# Car.net
KiCad netlist of a schematic drawn in Altium Designer
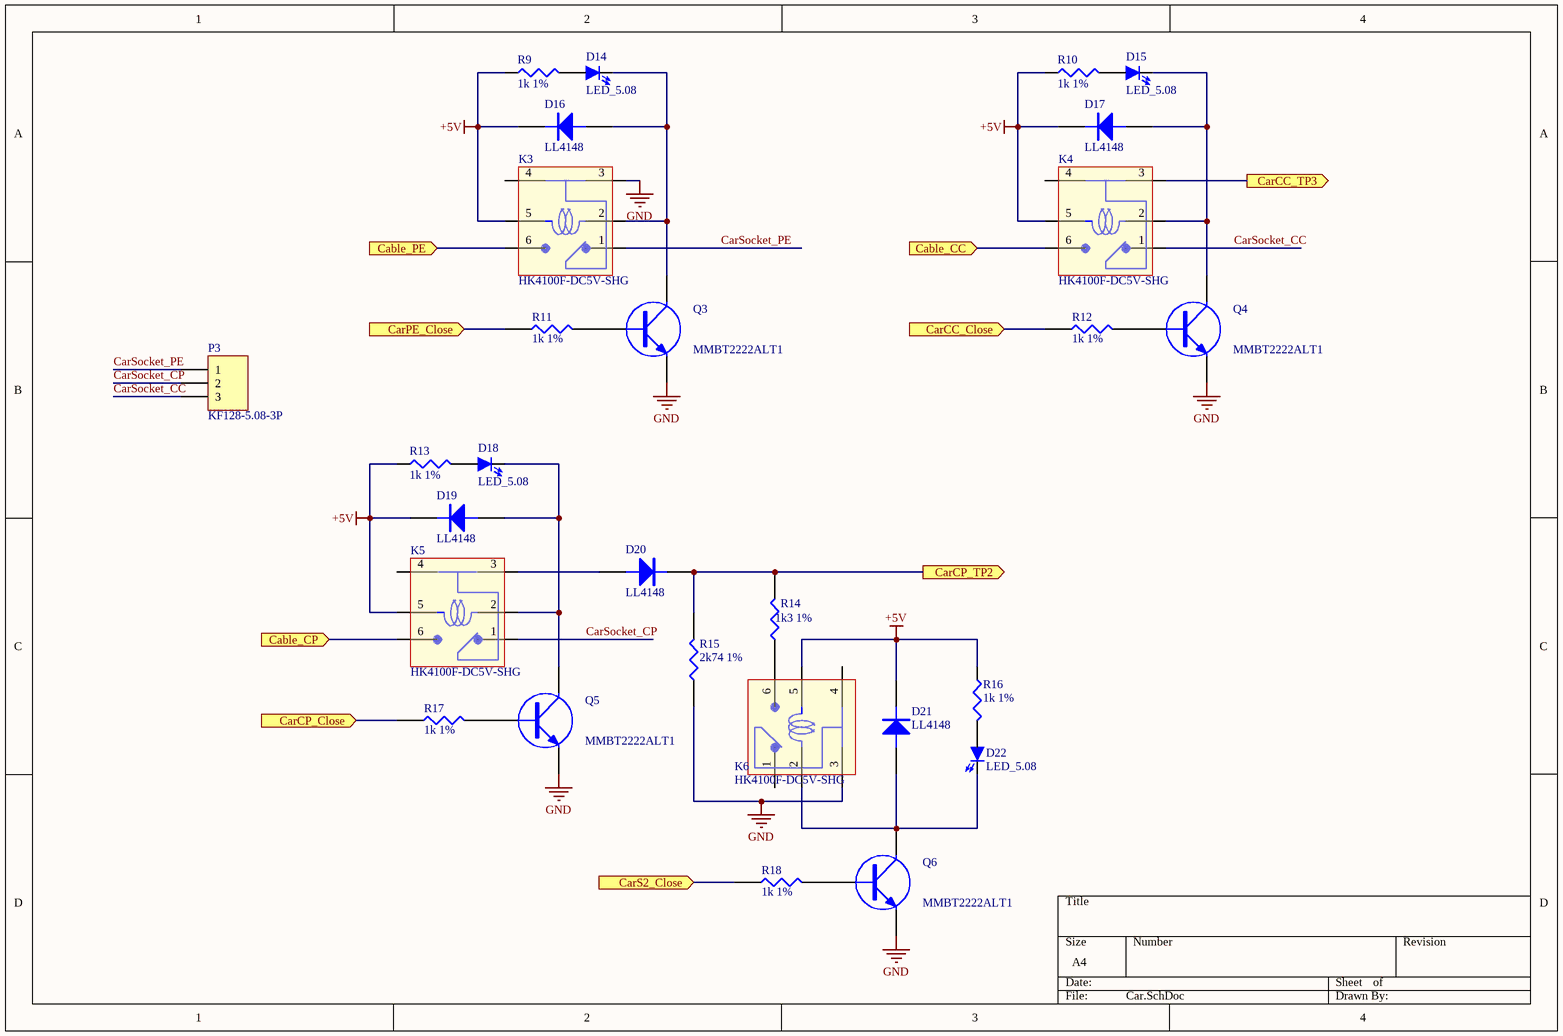
[diagram p0: Car.SchDoc]

(export (version "E")
  (design (tool "Eeschema 10.0.6"))
  (components
    (comp (ref "D14")
      (value "LED_5.08")
      (footprint "UserPcbLib:LED5.08/2.54-2")
      (description "Through hole LED dia.5.08")
      (libsource (lib "UserSchlib") (part "LED_5.08"))
    )
    (comp (ref "D15")
      (value "LED_5.08")
      (footprint "UserPcbLib:LED5.08/2.54-2")
      (description "Through hole LED dia.5.08")
      (libsource (lib "UserSchlib") (part "LED_5.08"))
    )
    (comp (ref "D16")
      (value "LL4148")
      (footprint "MELF - Diode:MELF-D3513-1405")
      (description "Diode")
      (libsource (lib "*") (part "DIODE"))
    )
    (comp (ref "D17")
      (value "LL4148")
      (footprint "MELF - Diode:MELF-D3513-1405")
      (description "Diode")
      (libsource (lib "*") (part "DIODE"))
    )
    (comp (ref "D18")
      (value "LED_5.08")
      (footprint "UserPcbLib:LED5.08/2.54-2")
      (description "Through hole LED dia.5.08")
      (libsource (lib "UserSchlib") (part "LED_5.08"))
    )
    (comp (ref "D19")
      (value "LL4148")
      (footprint "MELF - Diode:MELF-D3513-1405")
      (description "Diode")
      (libsource (lib "*") (part "DIODE"))
    )
    (comp (ref "D20")
      (value "LL4148")
      (footprint "MELF - Diode:MELF-D3513-1405")
      (description "Diode")
      (libsource (lib "*") (part "DIODE"))
    )
    (comp (ref "D21")
      (value "LL4148")
      (footprint "MELF - Diode:MELF-D3513-1405")
      (description "Diode")
      (libsource (lib "*") (part "DIODE"))
    )
    (comp (ref "D22")
      (value "LED_5.08")
      (footprint "UserPcbLib:LED5.08/2.54-2")
      (description "Through hole LED dia.5.08")
      (libsource (lib "UserSchlib") (part "LED_5.08"))
    )
    (comp (ref "K3")
      (value "HK4100F-DC5V-SHG")
      (footprint "UserPcbLib:HK4100F-DC5V-SHG")
      (description "HUI KE DC5V relay")
      (libsource (lib "UserSchlib") (part "HK4100F-DC5V-SHG"))
    )
    (comp (ref "K4")
      (value "HK4100F-DC5V-SHG")
      (footprint "UserPcbLib:HK4100F-DC5V-SHG")
      (description "HUI KE DC5V relay")
      (libsource (lib "UserSchlib") (part "HK4100F-DC5V-SHG"))
    )
    (comp (ref "K5")
      (value "HK4100F-DC5V-SHG")
      (footprint "UserPcbLib:HK4100F-DC5V-SHG")
      (description "HUI KE DC5V relay")
      (libsource (lib "UserSchlib") (part "HK4100F-DC5V-SHG"))
    )
    (comp (ref "K6")
      (value "HK4100F-DC5V-SHG")
      (footprint "UserPcbLib:HK4100F-DC5V-SHG")
      (description "HUI KE DC5V relay")
      (libsource (lib "") (part "HK4100F-DC5V-SHG_1"))
    )
    (comp (ref "P3")
      (value "KF128-5.08-3P")
      (footprint "UserPcbLib:KF128-5.08-3P")
      (description "Car socket connector")
      (fields (field (name "PUBLISHER") "Altium Limited"))
      (libsource (lib "Miscellaneous Connectors") (part "Header 3"))
    )
    (comp (ref "Q3") (value "MMBT2222ALT1") (footprint "SOT23_M:SOT23-3M") (libsource (lib "*") (part "NPN")))
    (comp (ref "Q4") (value "MMBT2222ALT1") (footprint "SOT23_M:SOT23-3M") (libsource (lib "*") (part "NPN")))
    (comp (ref "Q5") (value "MMBT2222ALT1") (footprint "SOT23_M:SOT23-3M") (libsource (lib "*") (part "NPN")))
    (comp (ref "Q6") (value "MMBT2222ALT1") (footprint "SOT23_M:SOT23-3M") (libsource (lib "*") (part "NPN")))
    (comp (ref "R9")
      (value "1k 1%")
      (footprint "Chip_Resistor_N:RESC2012N")
      (description "Resistor")
      (libsource (lib "Miscellaneous Devices") (part "Res3"))
    )
    (comp (ref "R10")
      (value "1k 1%")
      (footprint "Chip_Resistor_N:RESC2012N")
      (description "Resistor")
      (libsource (lib "Miscellaneous Devices") (part "Res3"))
    )
    (comp (ref "R11")
      (value "1k 1%")
      (footprint "Chip_Resistor_N:RESC2012N")
      (libsource (lib "*") (part "RES1"))
    )
    (comp (ref "R12")
      (value "1k 1%")
      (footprint "Chip_Resistor_N:RESC2012N")
      (libsource (lib "*") (part "RES1"))
    )
    (comp (ref "R13")
      (value "1k 1%")
      (footprint "Chip_Resistor_N:RESC2012N")
      (description "Resistor")
      (libsource (lib "Miscellaneous Devices") (part "Res3"))
    )
    (comp (ref "R14")
      (value "1k3 1%")
      (footprint "Chip_Resistor_N:RESC2012N")
      (libsource (lib "*") (part "RES1"))
    )
    (comp (ref "R15")
      (value "2k74 1%")
      (footprint "Chip_Resistor_N:RESC2012N")
      (libsource (lib "*") (part "RES1"))
    )
    (comp (ref "R16")
      (value "1k 1%")
      (footprint "Chip_Resistor_N:RESC2012N")
      (description "Resistor")
      (libsource (lib "Miscellaneous Devices") (part "Res3"))
    )
    (comp (ref "R17")
      (value "1k 1%")
      (footprint "Chip_Resistor_N:RESC2012N")
      (libsource (lib "*") (part "RES1"))
    )
    (comp (ref "R18")
      (value "1k 1%")
      (footprint "Chip_Resistor_N:RESC2012N")
      (libsource (lib "*") (part "RES1"))
    )
  )
  (nets
    (net (code "1") (name "+5V") (class "Default")
      (node (ref "D16") (pin "2") (pinfunction "K_2") (pintype "passive"))
      (node (ref "D17") (pin "2") (pinfunction "K_2") (pintype "passive"))
      (node (ref "D19") (pin "2") (pinfunction "K_2") (pintype "passive"))
      (node (ref "D21") (pin "2") (pinfunction "K_2") (pintype "passive"))
      (node (ref "K3") (pin "5") (pinfunction "5_5") (pintype "passive"))
      (node (ref "K4") (pin "5") (pinfunction "5_5") (pintype "passive"))
      (node (ref "K5") (pin "5") (pinfunction "5_5") (pintype "passive"))
      (node (ref "K6") (pin "5") (pinfunction "5_5") (pintype "passive"))
      (node (ref "R10") (pin "1") (pinfunction "1_1") (pintype "passive"))
      (node (ref "R13") (pin "1") (pinfunction "1_1") (pintype "passive"))
      (node (ref "R16") (pin "1") (pinfunction "1_1") (pintype "passive"))
      (node (ref "R9") (pin "1") (pinfunction "1_1") (pintype "passive"))
    )
    (net (code "2") (name "/Cable_CC") (class "Default")
      (node (ref "K4") (pin "6") (pinfunction "6_6") (pintype "passive"))
    )
    (net (code "3") (name "/Cable_CP") (class "Default")
      (node (ref "K5") (pin "6") (pinfunction "6_6") (pintype "passive"))
    )
    (net (code "4") (name "/Cable_PE") (class "Default")
      (node (ref "K3") (pin "6") (pinfunction "6_6") (pintype "passive"))
    )
    (net (code "5") (name "/CarCC_Close") (class "Default")
      (node (ref "R12") (pin "1") (pinfunction "1_1") (pintype "passive"))
    )
    (net (code "6") (name "/CarCC_TP3") (class "Default")
      (node (ref "K4") (pin "3") (pinfunction "3_3") (pintype "passive"))
    )
    (net (code "7") (name "/CarCP_Close") (class "Default")
      (node (ref "R17") (pin "1") (pinfunction "1_1") (pintype "passive"))
    )
    (net (code "8") (name "/CarCP_TP2") (class "Default")
      (node (ref "D20") (pin "2") (pinfunction "K_2") (pintype "passive"))
      (node (ref "R14") (pin "2") (pinfunction "2_2") (pintype "passive"))
      (node (ref "R15") (pin "2") (pinfunction "2_2") (pintype "passive"))
    )
    (net (code "9") (name "/CarPE_Close") (class "Default")
      (node (ref "R11") (pin "1") (pinfunction "1_1") (pintype "passive"))
    )
    (net (code "10") (name "/CarS2_Close") (class "Default")
      (node (ref "R18") (pin "1") (pinfunction "1_1") (pintype "passive"))
    )
    (net (code "11") (name "/CarSocket_CC") (class "Default")
      (node (ref "K4") (pin "1") (pinfunction "1_1") (pintype "passive"))
      (node (ref "P3") (pin "3") (pinfunction "3_3") (pintype "passive"))
    )
    (net (code "12") (name "/CarSocket_CP") (class "Default")
      (node (ref "K5") (pin "1") (pinfunction "1_1") (pintype "passive"))
      (node (ref "P3") (pin "2") (pinfunction "2_2") (pintype "passive"))
    )
    (net (code "13") (name "/CarSocket_PE") (class "Default")
      (node (ref "K3") (pin "1") (pinfunction "1_1") (pintype "passive"))
      (node (ref "P3") (pin "1") (pinfunction "1_1") (pintype "passive"))
    )
    (net (code "14") (name "GND") (class "Default")
      (node (ref "K3") (pin "3") (pinfunction "3_3") (pintype "passive"))
      (node (ref "K6") (pin "3") (pinfunction "3_3") (pintype "passive"))
      (node (ref "Q3") (pin "2") (pinfunction "E_2") (pintype "passive"))
      (node (ref "Q4") (pin "2") (pinfunction "E_2") (pintype "passive"))
      (node (ref "Q5") (pin "2") (pinfunction "E_2") (pintype "passive"))
      (node (ref "Q6") (pin "2") (pinfunction "E_2") (pintype "passive"))
      (node (ref "R15") (pin "1") (pinfunction "1_1") (pintype "passive"))
    )
    (net (code "15") (name "Net-(D14-A)") (class "Default")
      (node (ref "D14") (pin "1") (pinfunction "A_1") (pintype "passive"))
      (node (ref "R9") (pin "2") (pinfunction "2_2") (pintype "passive"))
    )
    (net (code "16") (name "Net-(D14-K)") (class "Default")
      (node (ref "D14") (pin "2") (pinfunction "K_2") (pintype "passive"))
      (node (ref "D16") (pin "1") (pinfunction "A_1") (pintype "passive"))
      (node (ref "K3") (pin "2") (pinfunction "2_2") (pintype "passive"))
      (node (ref "Q3") (pin "3") (pinfunction "C_3") (pintype "passive"))
    )
    (net (code "17") (name "Net-(D15-A)") (class "Default")
      (node (ref "D15") (pin "1") (pinfunction "A_1") (pintype "passive"))
      (node (ref "R10") (pin "2") (pinfunction "2_2") (pintype "passive"))
    )
    (net (code "18") (name "Net-(D15-K)") (class "Default")
      (node (ref "D15") (pin "2") (pinfunction "K_2") (pintype "passive"))
      (node (ref "D17") (pin "1") (pinfunction "A_1") (pintype "passive"))
      (node (ref "K4") (pin "2") (pinfunction "2_2") (pintype "passive"))
      (node (ref "Q4") (pin "3") (pinfunction "C_3") (pintype "passive"))
    )
    (net (code "19") (name "Net-(D18-A)") (class "Default")
      (node (ref "D18") (pin "1") (pinfunction "A_1") (pintype "passive"))
      (node (ref "R13") (pin "2") (pinfunction "2_2") (pintype "passive"))
    )
    (net (code "20") (name "Net-(D18-K)") (class "Default")
      (node (ref "D18") (pin "2") (pinfunction "K_2") (pintype "passive"))
      (node (ref "D19") (pin "1") (pinfunction "A_1") (pintype "passive"))
      (node (ref "K5") (pin "2") (pinfunction "2_2") (pintype "passive"))
      (node (ref "Q5") (pin "3") (pinfunction "C_3") (pintype "passive"))
    )
    (net (code "21") (name "Net-(D20-A)") (class "Default")
      (node (ref "D20") (pin "1") (pinfunction "A_1") (pintype "passive"))
      (node (ref "K5") (pin "3") (pinfunction "3_3") (pintype "passive"))
    )
    (net (code "22") (name "Net-(D21-A)") (class "Default")
      (node (ref "D21") (pin "1") (pinfunction "A_1") (pintype "passive"))
      (node (ref "D22") (pin "2") (pinfunction "K_2") (pintype "passive"))
      (node (ref "K6") (pin "2") (pinfunction "2_2") (pintype "passive"))
      (node (ref "Q6") (pin "3") (pinfunction "C_3") (pintype "passive"))
    )
    (net (code "23") (name "Net-(D22-A)") (class "Default")
      (node (ref "D22") (pin "1") (pinfunction "A_1") (pintype "passive"))
      (node (ref "R16") (pin "2") (pinfunction "2_2") (pintype "passive"))
    )
    (net (code "24") (name "Net-(K6-Pad6)") (class "Default")
      (node (ref "K6") (pin "6") (pinfunction "6_6") (pintype "passive"))
      (node (ref "R14") (pin "1") (pinfunction "1_1") (pintype "passive"))
    )
    (net (code "25") (name "Net-(Q3-B)") (class "Default")
      (node (ref "Q3") (pin "1") (pinfunction "B_1") (pintype "passive"))
      (node (ref "R11") (pin "2") (pinfunction "2_2") (pintype "passive"))
    )
    (net (code "26") (name "Net-(Q4-B)") (class "Default")
      (node (ref "Q4") (pin "1") (pinfunction "B_1") (pintype "passive"))
      (node (ref "R12") (pin "2") (pinfunction "2_2") (pintype "passive"))
    )
    (net (code "27") (name "Net-(Q5-B)") (class "Default")
      (node (ref "Q5") (pin "1") (pinfunction "B_1") (pintype "passive"))
      (node (ref "R17") (pin "2") (pinfunction "2_2") (pintype "passive"))
    )
    (net (code "28") (name "Net-(Q6-B)") (class "Default")
      (node (ref "Q6") (pin "1") (pinfunction "B_1") (pintype "passive"))
      (node (ref "R18") (pin "2") (pinfunction "2_2") (pintype "passive"))
    )
    (net (code "29") (name "unconnected-(K3-Pad4)") (class "Default")
      (node (ref "K3") (pin "4") (pinfunction "4_4") (pintype "passive"))
    )
    (net (code "30") (name "unconnected-(K4-Pad4)") (class "Default")
      (node (ref "K4") (pin "4") (pinfunction "4_4") (pintype "passive"))
    )
    (net (code "31") (name "unconnected-(K5-Pad4)") (class "Default")
      (node (ref "K5") (pin "4") (pinfunction "4_4") (pintype "passive"))
    )
    (net (code "32") (name "unconnected-(K6-Pad1)") (class "Default")
      (node (ref "K6") (pin "1") (pinfunction "1_1") (pintype "passive"))
    )
    (net (code "33") (name "unconnected-(K6-Pad4)") (class "Default")
      (node (ref "K6") (pin "4") (pinfunction "4_4") (pintype "passive"))
    )
  )
)
